# 02_memory.net
KiCad netlist of a schematic drawn in Altium Designer
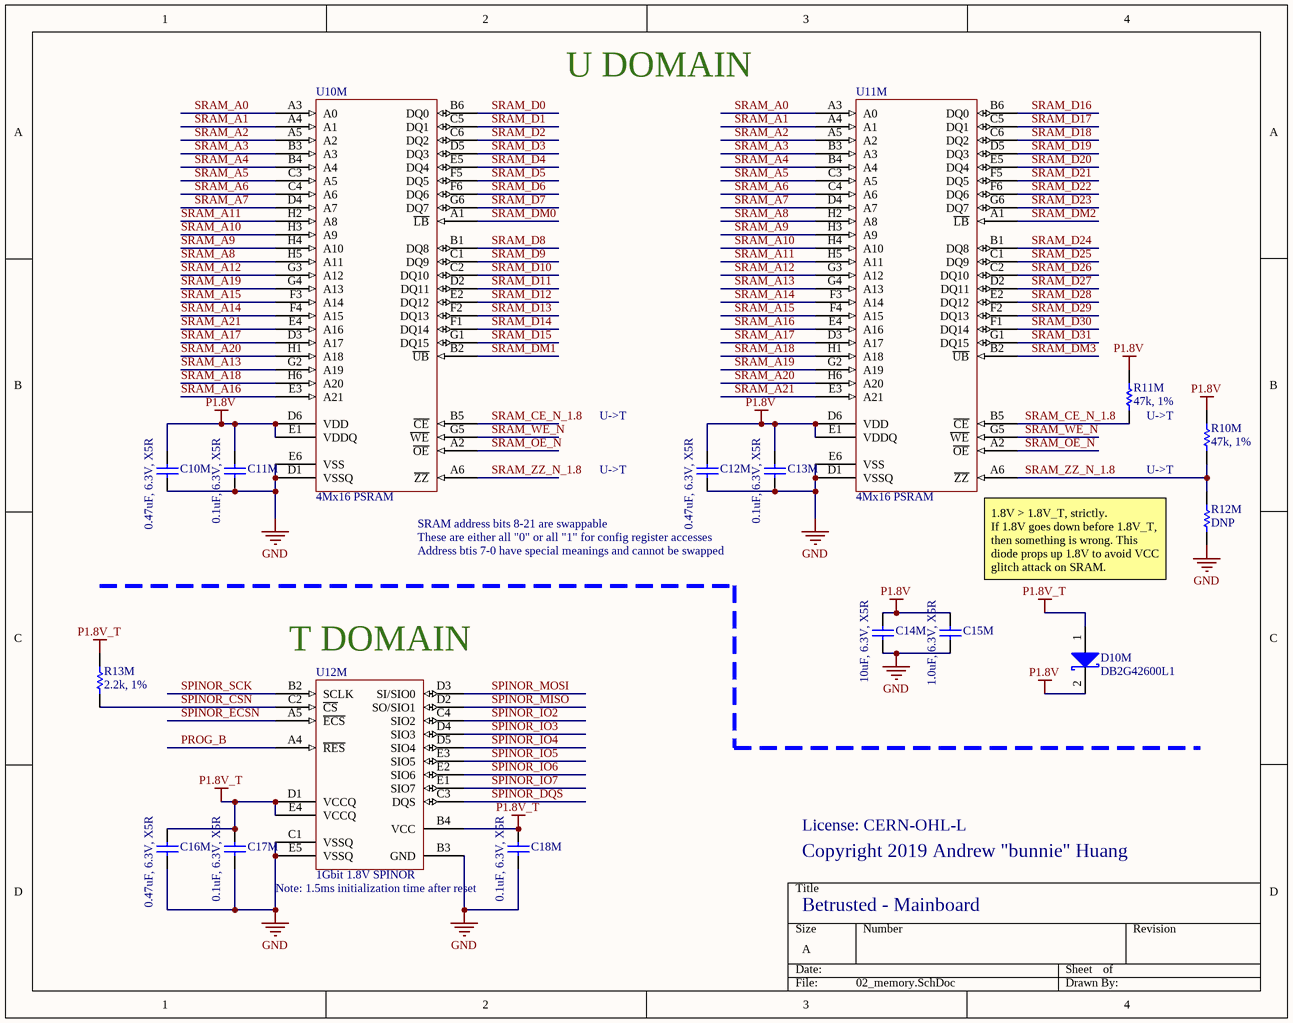
[diagram p0: 02_memory.SchDoc]

(export (version "E")
  (design (tool "Eeschema 10.0.6"))
  (components
    (comp (ref "C10M")
      (value "0.47uF, 6.3V, X5R")
      (footprint "B_CAP0201")
      (description "Capacitor (Semiconductor SIM Model)")
      (fields (field (name "MPN") "CL03A474KQ3NNNH"))
      (libsource (lib "Miscellaneous Devices") (part "Cap Semi"))
    )
    (comp (ref "C11M")
      (value "0.1uF, 6.3V, X5R")
      (footprint "B_CAP0201")
      (description "Capacitor (Semiconductor SIM Model)")
      (fields (field (name "MPN") "CL03A104KQ3NNNC"))
      (libsource (lib "Miscellaneous Devices") (part "Cap Semi"))
    )
    (comp (ref "C12M")
      (value "0.47uF, 6.3V, X5R")
      (footprint "B_CAP0201")
      (description "Capacitor (Semiconductor SIM Model)")
      (fields (field (name "MPN") "CL03A474KQ3NNNH"))
      (libsource (lib "Miscellaneous Devices") (part "Cap Semi"))
    )
    (comp (ref "C13M")
      (value "0.1uF, 6.3V, X5R")
      (footprint "B_CAP0201")
      (description "Capacitor (Semiconductor SIM Model)")
      (fields (field (name "MPN") "CL03A104KQ3NNNC"))
      (libsource (lib "Miscellaneous Devices") (part "Cap Semi"))
    )
    (comp (ref "C14M")
      (value "10uF, 6.3V, X5R")
      (footprint "B_CAP0603")
      (description "Capacitor (Semiconductor SIM Model)")
      (fields (field (name "MPN") "CL10A106MQ8NNNC"))
      (libsource (lib "Miscellaneous Devices") (part "Cap Semi"))
    )
    (comp (ref "C15M")
      (value "1.0uF, 6.3V, X5R")
      (footprint "B_CAP0201")
      (description "Capacitor (Semiconductor SIM Model)")
      (fields (field (name "MPN") "GRM033R60J105MEA2D"))
      (libsource (lib "Miscellaneous Devices") (part "Cap Semi"))
    )
    (comp (ref "C16M")
      (value "0.47uF, 6.3V, X5R")
      (footprint "B_CAP0201")
      (description "Capacitor (Semiconductor SIM Model)")
      (fields (field (name "MPN") "CL03A474KQ3NNNH"))
      (libsource (lib "Miscellaneous Devices") (part "Cap Semi"))
    )
    (comp (ref "C17M")
      (value "0.1uF, 6.3V, X5R")
      (footprint "B_CAP0201")
      (description "Capacitor (Semiconductor SIM Model)")
      (fields (field (name "MPN") "CL03A104KQ3NNNC"))
      (libsource (lib "Miscellaneous Devices") (part "Cap Semi"))
    )
    (comp (ref "C18M")
      (value "0.1uF, 6.3V, X5R")
      (footprint "B_CAP0201")
      (description "Capacitor (Semiconductor SIM Model)")
      (fields (field (name "MPN") "CL03A104KQ3NNNC"))
      (libsource (lib "Miscellaneous Devices") (part "Cap Semi"))
    )
    (comp (ref "D10M")
      (value "DB2G42600L1")
      (footprint "B_DIO0402")
      (description "Schottky Rectifier")
      (libsource (lib "Miscellaneous Devices") (part "Diode 11DQ03"))
    )
    (comp (ref "R10M")
      (value "47k, 1%")
      (footprint "B_RES0201")
      (description "Resistor")
      (fields (field (name "MPN") "ANY"))
      (libsource (lib "Miscellaneous Devices") (part "Res1"))
    )
    (comp (ref "R11M")
      (value "47k, 1%")
      (footprint "B_RES0201")
      (description "Resistor")
      (fields (field (name "MPN") "ANY"))
      (libsource (lib "Miscellaneous Devices") (part "Res1"))
    )
    (comp (ref "R12M")
      (value "DNP")
      (footprint "B_RES0201")
      (description "Resistor")
      (fields (field (name "MPN") "ANY"))
      (libsource (lib "Miscellaneous Devices") (part "Res1"))
    )
    (comp (ref "R13M")
      (value "2.2k, 1%")
      (footprint "B_RES0201")
      (description "Resistor")
      (fields (field (name "MPN") "ANY"))
      (libsource (lib "Miscellaneous Devices") (part "Res1"))
    )
    (comp (ref "U10M")
      (value "4Mx16 PSRAM")
      (footprint "BGA48C75P6X8_600X800X120")
      (fields (field (name "MPN") "IS66WVE4M16EALL-70BLI"))
      (libsource (lib "altium-import") (part "root_0_IS66WVE4M16_"))
    )
    (comp (ref "U11M")
      (value "4Mx16 PSRAM")
      (footprint "BGA48C75P6X8_600X800X120")
      (fields (field (name "MPN") "IS66WVE4M16EALL-70BLI"))
      (libsource (lib "altium-import") (part "root_0_IS66WVE4M16_"))
    )
    (comp (ref "U12M")
      (value "1Gbit 1.8V SPINOR")
      (footprint "BGA24C100P5X5_600X800X120")
      (description "1.8V 1Gbit x1/x8 OctaFlash SPINOR")
      (fields (field (name "MPN") "MX66UM1G45GXDI00"))
      (libsource (lib "commonsch-new") (part "MX66UM1G45G"))
    )
  )
  (nets
    (net (code "1") (name "/PROG_B") (class "Default")
      (node (ref "U12M") (pin "A4") (pinfunction "~{RES}_A4") (pintype "input"))
    )
    (net (code "2") (name "/SPINOR_CSN") (class "Default")
      (node (ref "R13M") (pin "1") (pinfunction "1_1") (pintype "passive"))
      (node (ref "U12M") (pin "C2") (pinfunction "~{CS}_C2") (pintype "input"))
    )
    (net (code "3") (name "/SPINOR_DQS") (class "Default")
      (node (ref "U12M") (pin "C3") (pinfunction "DQS_C3") (pintype "bidirectional"))
    )
    (net (code "4") (name "/SPINOR_ECSN") (class "Default")
      (node (ref "U12M") (pin "A5") (pinfunction "~{ECS}_A5") (pintype "input"))
    )
    (net (code "5") (name "/SPINOR_IO2") (class "Default")
      (node (ref "U12M") (pin "C4") (pinfunction "SIO2_C4") (pintype "bidirectional"))
    )
    (net (code "6") (name "/SPINOR_IO3") (class "Default")
      (node (ref "U12M") (pin "D4") (pinfunction "SIO3_D4") (pintype "bidirectional"))
    )
    (net (code "7") (name "/SPINOR_IO4") (class "Default")
      (node (ref "U12M") (pin "D5") (pinfunction "SIO4_D5") (pintype "bidirectional"))
    )
    (net (code "8") (name "/SPINOR_IO5") (class "Default")
      (node (ref "U12M") (pin "E3") (pinfunction "SIO5_E3") (pintype "bidirectional"))
    )
    (net (code "9") (name "/SPINOR_IO6") (class "Default")
      (node (ref "U12M") (pin "E2") (pinfunction "SIO6_E2") (pintype "bidirectional"))
    )
    (net (code "10") (name "/SPINOR_IO7") (class "Default")
      (node (ref "U12M") (pin "E1") (pinfunction "SIO7_E1") (pintype "bidirectional"))
    )
    (net (code "11") (name "/SPINOR_MISO") (class "Default")
      (node (ref "U12M") (pin "D2") (pinfunction "SO/SIO1_D2") (pintype "bidirectional"))
    )
    (net (code "12") (name "/SPINOR_MOSI") (class "Default")
      (node (ref "U12M") (pin "D3") (pinfunction "SI/SIO0_D3") (pintype "bidirectional"))
    )
    (net (code "13") (name "/SPINOR_SCK") (class "Default")
      (node (ref "U12M") (pin "B2") (pinfunction "SCLK_B2") (pintype "input"))
    )
    (net (code "14") (name "/SRAM_A0") (class "Default")
      (node (ref "U10M") (pin "A3") (pinfunction "A0_A3") (pintype "input"))
      (node (ref "U11M") (pin "A3") (pinfunction "A0_A3") (pintype "input"))
    )
    (net (code "15") (name "/SRAM_A1") (class "Default")
      (node (ref "U10M") (pin "A4") (pinfunction "A1_A4") (pintype "input"))
      (node (ref "U11M") (pin "A4") (pinfunction "A1_A4") (pintype "input"))
    )
    (net (code "16") (name "/SRAM_A2") (class "Default")
      (node (ref "U10M") (pin "A5") (pinfunction "A2_A5") (pintype "input"))
      (node (ref "U11M") (pin "A5") (pinfunction "A2_A5") (pintype "input"))
    )
    (net (code "17") (name "/SRAM_A3") (class "Default")
      (node (ref "U10M") (pin "B3") (pinfunction "A3_B3") (pintype "input"))
      (node (ref "U11M") (pin "B3") (pinfunction "A3_B3") (pintype "input"))
    )
    (net (code "18") (name "/SRAM_A4") (class "Default")
      (node (ref "U10M") (pin "B4") (pinfunction "A4_B4") (pintype "input"))
      (node (ref "U11M") (pin "B4") (pinfunction "A4_B4") (pintype "input"))
    )
    (net (code "19") (name "/SRAM_A5") (class "Default")
      (node (ref "U10M") (pin "C3") (pinfunction "A5_C3") (pintype "input"))
      (node (ref "U11M") (pin "C3") (pinfunction "A5_C3") (pintype "input"))
    )
    (net (code "20") (name "/SRAM_A6") (class "Default")
      (node (ref "U10M") (pin "C4") (pinfunction "A6_C4") (pintype "input"))
      (node (ref "U11M") (pin "C4") (pinfunction "A6_C4") (pintype "input"))
    )
    (net (code "21") (name "/SRAM_A7") (class "Default")
      (node (ref "U10M") (pin "D4") (pinfunction "A7_D4") (pintype "input"))
      (node (ref "U11M") (pin "D4") (pinfunction "A7_D4") (pintype "input"))
    )
    (net (code "22") (name "/SRAM_A8") (class "Default")
      (node (ref "U10M") (pin "H5") (pinfunction "A11_H5") (pintype "input"))
      (node (ref "U11M") (pin "H2") (pinfunction "A8_H2") (pintype "input"))
    )
    (net (code "23") (name "/SRAM_A9") (class "Default")
      (node (ref "U10M") (pin "H4") (pinfunction "A10_H4") (pintype "input"))
      (node (ref "U11M") (pin "H3") (pinfunction "A9_H3") (pintype "input"))
    )
    (net (code "24") (name "/SRAM_A10") (class "Default")
      (node (ref "U10M") (pin "H3") (pinfunction "A9_H3") (pintype "input"))
      (node (ref "U11M") (pin "H4") (pinfunction "A10_H4") (pintype "input"))
    )
    (net (code "25") (name "/SRAM_A11") (class "Default")
      (node (ref "U10M") (pin "H2") (pinfunction "A8_H2") (pintype "input"))
      (node (ref "U11M") (pin "H5") (pinfunction "A11_H5") (pintype "input"))
    )
    (net (code "26") (name "/SRAM_A12") (class "Default")
      (node (ref "U10M") (pin "G3") (pinfunction "A12_G3") (pintype "input"))
      (node (ref "U11M") (pin "G3") (pinfunction "A12_G3") (pintype "input"))
    )
    (net (code "27") (name "/SRAM_A13") (class "Default")
      (node (ref "U10M") (pin "G2") (pinfunction "A19_G2") (pintype "input"))
      (node (ref "U11M") (pin "G4") (pinfunction "A13_G4") (pintype "input"))
    )
    (net (code "28") (name "/SRAM_A14") (class "Default")
      (node (ref "U10M") (pin "F4") (pinfunction "A15_F4") (pintype "input"))
      (node (ref "U11M") (pin "F3") (pinfunction "A14_F3") (pintype "input"))
    )
    (net (code "29") (name "/SRAM_A15") (class "Default")
      (node (ref "U10M") (pin "F3") (pinfunction "A14_F3") (pintype "input"))
      (node (ref "U11M") (pin "F4") (pinfunction "A15_F4") (pintype "input"))
    )
    (net (code "30") (name "/SRAM_A16") (class "Default")
      (node (ref "U10M") (pin "E3") (pinfunction "A21_E3") (pintype "input"))
      (node (ref "U11M") (pin "E4") (pinfunction "A16_E4") (pintype "input"))
    )
    (net (code "31") (name "/SRAM_A17") (class "Default")
      (node (ref "U10M") (pin "D3") (pinfunction "A17_D3") (pintype "input"))
      (node (ref "U11M") (pin "D3") (pinfunction "A17_D3") (pintype "input"))
    )
    (net (code "32") (name "/SRAM_A18") (class "Default")
      (node (ref "U10M") (pin "H6") (pinfunction "A20_H6") (pintype "input"))
      (node (ref "U11M") (pin "H1") (pinfunction "A18_H1") (pintype "input"))
    )
    (net (code "33") (name "/SRAM_A19") (class "Default")
      (node (ref "U10M") (pin "G4") (pinfunction "A13_G4") (pintype "input"))
      (node (ref "U11M") (pin "G2") (pinfunction "A19_G2") (pintype "input"))
    )
    (net (code "34") (name "/SRAM_A20") (class "Default")
      (node (ref "U10M") (pin "H1") (pinfunction "A18_H1") (pintype "input"))
      (node (ref "U11M") (pin "H6") (pinfunction "A20_H6") (pintype "input"))
    )
    (net (code "35") (name "/SRAM_A21") (class "Default")
      (node (ref "U10M") (pin "E4") (pinfunction "A16_E4") (pintype "input"))
      (node (ref "U11M") (pin "E3") (pinfunction "A21_E3") (pintype "input"))
    )
    (net (code "36") (name "/SRAM_CE_N_1.8") (class "Default")
      (node (ref "R11M") (pin "2") (pinfunction "2_2") (pintype "passive"))
      (node (ref "U10M") (pin "B5") (pinfunction "~{CE}_B5") (pintype "input"))
      (node (ref "U11M") (pin "B5") (pinfunction "~{CE}_B5") (pintype "input"))
    )
    (net (code "37") (name "/SRAM_D0") (class "Default")
      (node (ref "U10M") (pin "B6") (pinfunction "DQ0_B6") (pintype "bidirectional"))
    )
    (net (code "38") (name "/SRAM_D1") (class "Default")
      (node (ref "U10M") (pin "C5") (pinfunction "DQ1_C5") (pintype "bidirectional"))
    )
    (net (code "39") (name "/SRAM_D2") (class "Default")
      (node (ref "U10M") (pin "C6") (pinfunction "DQ2_C6") (pintype "bidirectional"))
    )
    (net (code "40") (name "/SRAM_D3") (class "Default")
      (node (ref "U10M") (pin "D5") (pinfunction "DQ3_D5") (pintype "bidirectional"))
    )
    (net (code "41") (name "/SRAM_D4") (class "Default")
      (node (ref "U10M") (pin "E5") (pinfunction "DQ4_E5") (pintype "bidirectional"))
    )
    (net (code "42") (name "/SRAM_D5") (class "Default")
      (node (ref "U10M") (pin "F5") (pinfunction "DQ5_F5") (pintype "bidirectional"))
    )
    (net (code "43") (name "/SRAM_D6") (class "Default")
      (node (ref "U10M") (pin "F6") (pinfunction "DQ6_F6") (pintype "bidirectional"))
    )
    (net (code "44") (name "/SRAM_D7") (class "Default")
      (node (ref "U10M") (pin "G6") (pinfunction "DQ7_G6") (pintype "bidirectional"))
    )
    (net (code "45") (name "/SRAM_D8") (class "Default")
      (node (ref "U10M") (pin "B1") (pinfunction "DQ8_B1") (pintype "bidirectional"))
    )
    (net (code "46") (name "/SRAM_D9") (class "Default")
      (node (ref "U10M") (pin "C1") (pinfunction "DQ9_C1") (pintype "bidirectional"))
    )
    (net (code "47") (name "/SRAM_D10") (class "Default")
      (node (ref "U10M") (pin "C2") (pinfunction "DQ10_C2") (pintype "bidirectional"))
    )
    (net (code "48") (name "/SRAM_D11") (class "Default")
      (node (ref "U10M") (pin "D2") (pinfunction "DQ11_D2") (pintype "bidirectional"))
    )
    (net (code "49") (name "/SRAM_D12") (class "Default")
      (node (ref "U10M") (pin "E2") (pinfunction "DQ12_E2") (pintype "bidirectional"))
    )
    (net (code "50") (name "/SRAM_D13") (class "Default")
      (node (ref "U10M") (pin "F2") (pinfunction "DQ13_F2") (pintype "bidirectional"))
    )
    (net (code "51") (name "/SRAM_D14") (class "Default")
      (node (ref "U10M") (pin "F1") (pinfunction "DQ14_F1") (pintype "bidirectional"))
    )
    (net (code "52") (name "/SRAM_D15") (class "Default")
      (node (ref "U10M") (pin "G1") (pinfunction "DQ15_G1") (pintype "bidirectional"))
    )
    (net (code "53") (name "/SRAM_D16") (class "Default")
      (node (ref "U11M") (pin "B6") (pinfunction "DQ0_B6") (pintype "bidirectional"))
    )
    (net (code "54") (name "/SRAM_D17") (class "Default")
      (node (ref "U11M") (pin "C5") (pinfunction "DQ1_C5") (pintype "bidirectional"))
    )
    (net (code "55") (name "/SRAM_D18") (class "Default")
      (node (ref "U11M") (pin "C6") (pinfunction "DQ2_C6") (pintype "bidirectional"))
    )
    (net (code "56") (name "/SRAM_D19") (class "Default")
      (node (ref "U11M") (pin "D5") (pinfunction "DQ3_D5") (pintype "bidirectional"))
    )
    (net (code "57") (name "/SRAM_D20") (class "Default")
      (node (ref "U11M") (pin "E5") (pinfunction "DQ4_E5") (pintype "bidirectional"))
    )
    (net (code "58") (name "/SRAM_D21") (class "Default")
      (node (ref "U11M") (pin "F5") (pinfunction "DQ5_F5") (pintype "bidirectional"))
    )
    (net (code "59") (name "/SRAM_D22") (class "Default")
      (node (ref "U11M") (pin "F6") (pinfunction "DQ6_F6") (pintype "bidirectional"))
    )
    (net (code "60") (name "/SRAM_D23") (class "Default")
      (node (ref "U11M") (pin "G6") (pinfunction "DQ7_G6") (pintype "bidirectional"))
    )
    (net (code "61") (name "/SRAM_D24") (class "Default")
      (node (ref "U11M") (pin "B1") (pinfunction "DQ8_B1") (pintype "bidirectional"))
    )
    (net (code "62") (name "/SRAM_D25") (class "Default")
      (node (ref "U11M") (pin "C1") (pinfunction "DQ9_C1") (pintype "bidirectional"))
    )
    (net (code "63") (name "/SRAM_D26") (class "Default")
      (node (ref "U11M") (pin "C2") (pinfunction "DQ10_C2") (pintype "bidirectional"))
    )
    (net (code "64") (name "/SRAM_D27") (class "Default")
      (node (ref "U11M") (pin "D2") (pinfunction "DQ11_D2") (pintype "bidirectional"))
    )
    (net (code "65") (name "/SRAM_D28") (class "Default")
      (node (ref "U11M") (pin "E2") (pinfunction "DQ12_E2") (pintype "bidirectional"))
    )
    (net (code "66") (name "/SRAM_D29") (class "Default")
      (node (ref "U11M") (pin "F2") (pinfunction "DQ13_F2") (pintype "bidirectional"))
    )
    (net (code "67") (name "/SRAM_D30") (class "Default")
      (node (ref "U11M") (pin "F1") (pinfunction "DQ14_F1") (pintype "bidirectional"))
    )
    (net (code "68") (name "/SRAM_D31") (class "Default")
      (node (ref "U11M") (pin "G1") (pinfunction "DQ15_G1") (pintype "bidirectional"))
    )
    (net (code "69") (name "/SRAM_DM0") (class "Default")
      (node (ref "U10M") (pin "A1") (pinfunction "~{LB}_A1") (pintype "input"))
    )
    (net (code "70") (name "/SRAM_DM1") (class "Default")
      (node (ref "U10M") (pin "B2") (pinfunction "~{UB}_B2") (pintype "input"))
    )
    (net (code "71") (name "/SRAM_DM2") (class "Default")
      (node (ref "U11M") (pin "A1") (pinfunction "~{LB}_A1") (pintype "input"))
    )
    (net (code "72") (name "/SRAM_DM3") (class "Default")
      (node (ref "U11M") (pin "B2") (pinfunction "~{UB}_B2") (pintype "input"))
    )
    (net (code "73") (name "/SRAM_OE_N") (class "Default")
      (node (ref "U10M") (pin "A2") (pinfunction "~{OE}_A2") (pintype "input"))
      (node (ref "U11M") (pin "A2") (pinfunction "~{OE}_A2") (pintype "input"))
    )
    (net (code "74") (name "/SRAM_WE_N") (class "Default")
      (node (ref "U10M") (pin "G5") (pinfunction "~{WE}_G5") (pintype "input"))
      (node (ref "U11M") (pin "G5") (pinfunction "~{WE}_G5") (pintype "input"))
    )
    (net (code "75") (name "/SRAM_ZZ_N_1.8") (class "Default")
      (node (ref "R10M") (pin "2") (pinfunction "2_2") (pintype "passive"))
      (node (ref "R12M") (pin "1") (pinfunction "1_1") (pintype "passive"))
      (node (ref "U10M") (pin "A6") (pinfunction "~{ZZ}_A6") (pintype "input"))
      (node (ref "U11M") (pin "A6") (pinfunction "~{ZZ}_A6") (pintype "input"))
    )
    (net (code "76") (name "GND") (class "Default")
      (node (ref "C10M") (pin "2") (pinfunction "2_2") (pintype "passive"))
      (node (ref "C11M") (pin "2") (pinfunction "2_2") (pintype "passive"))
      (node (ref "C12M") (pin "2") (pinfunction "2_2") (pintype "passive"))
      (node (ref "C13M") (pin "2") (pinfunction "2_2") (pintype "passive"))
      (node (ref "C14M") (pin "2") (pinfunction "2_2") (pintype "passive"))
      (node (ref "C15M") (pin "1") (pinfunction "1_1") (pintype "passive"))
      (node (ref "C16M") (pin "2") (pinfunction "2_2") (pintype "passive"))
      (node (ref "C17M") (pin "2") (pinfunction "2_2") (pintype "passive"))
      (node (ref "C18M") (pin "2") (pinfunction "2_2") (pintype "passive"))
      (node (ref "R12M") (pin "2") (pinfunction "2_2") (pintype "passive"))
      (node (ref "U10M") (pin "D1") (pinfunction "VSSQ_D1") (pintype "power_in"))
      (node (ref "U10M") (pin "E6") (pinfunction "VSS_E6") (pintype "power_in"))
      (node (ref "U11M") (pin "D1") (pinfunction "VSSQ_D1") (pintype "power_in"))
      (node (ref "U11M") (pin "E6") (pinfunction "VSS_E6") (pintype "power_in"))
      (node (ref "U12M") (pin "B3") (pinfunction "GND_B3") (pintype "power_in"))
      (node (ref "U12M") (pin "C1") (pinfunction "VSSQ_C1") (pintype "power_in"))
      (node (ref "U12M") (pin "E5") (pinfunction "VSSQ_E5") (pintype "power_in"))
    )
    (net (code "77") (name "P1.8V") (class "Default")
      (node (ref "C10M") (pin "1") (pinfunction "1_1") (pintype "passive"))
      (node (ref "C11M") (pin "1") (pinfunction "1_1") (pintype "passive"))
      (node (ref "C12M") (pin "1") (pinfunction "1_1") (pintype "passive"))
      (node (ref "C13M") (pin "1") (pinfunction "1_1") (pintype "passive"))
      (node (ref "C14M") (pin "1") (pinfunction "1_1") (pintype "passive"))
      (node (ref "C15M") (pin "2") (pinfunction "2_2") (pintype "passive"))
      (node (ref "D10M") (pin "2") (pinfunction "K_2") (pintype "passive"))
      (node (ref "R10M") (pin "1") (pinfunction "1_1") (pintype "passive"))
      (node (ref "R11M") (pin "1") (pinfunction "1_1") (pintype "passive"))
      (node (ref "U10M") (pin "D6") (pinfunction "VDD_D6") (pintype "power_in"))
      (node (ref "U10M") (pin "E1") (pinfunction "VDDQ_E1") (pintype "power_in"))
      (node (ref "U11M") (pin "D6") (pinfunction "VDD_D6") (pintype "power_in"))
      (node (ref "U11M") (pin "E1") (pinfunction "VDDQ_E1") (pintype "power_in"))
    )
    (net (code "78") (name "P1.8V_T") (class "Default")
      (node (ref "C16M") (pin "1") (pinfunction "1_1") (pintype "passive"))
      (node (ref "C17M") (pin "1") (pinfunction "1_1") (pintype "passive"))
      (node (ref "C18M") (pin "1") (pinfunction "1_1") (pintype "passive"))
      (node (ref "D10M") (pin "1") (pinfunction "A_1") (pintype "passive"))
      (node (ref "R13M") (pin "2") (pinfunction "2_2") (pintype "passive"))
      (node (ref "U12M") (pin "B4") (pinfunction "VCC_B4") (pintype "power_in"))
      (node (ref "U12M") (pin "D1") (pinfunction "VCCQ_D1") (pintype "power_in"))
      (node (ref "U12M") (pin "E4") (pinfunction "VCCQ_E4") (pintype "power_in"))
    )
  )
)
